# ampnshift.net
KiCad netlist of a schematic drawn in Altium Designer
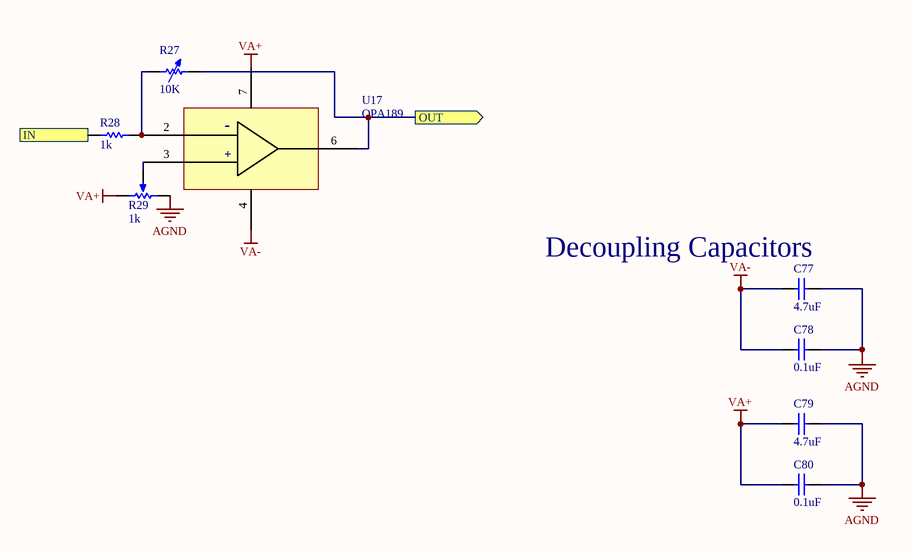
[diagram p0: ampnshift.SchDoc]

(export (version "E")
  (design (tool "Eeschema 10.0.6"))
  (components
    (comp (ref "C77")
      (value "4.7uF")
      (footprint "STD_0805_C")
      (description "Capacitor, 4.7uF, 0805")
      (libsource (lib "Arturo_Approved") (part "CL21A475KAQNNNE"))
    )
    (comp (ref "C78")
      (value "0.1uF")
      (footprint "STD_0805_C")
      (description "Capacitor, 0.1uF, 0805")
      (libsource (lib "Arturo_Approved") (part "CL21B104KACNNNC"))
    )
    (comp (ref "C79")
      (value "4.7uF")
      (footprint "STD_0805_C")
      (description "Capacitor, 4.7uF, 0805")
      (libsource (lib "Arturo_Approved") (part "CL21A475KAQNNNE"))
    )
    (comp (ref "C80")
      (value "0.1uF")
      (footprint "STD_0805_C")
      (description "Capacitor, 0.1uF, 0805")
      (libsource (lib "Arturo_Approved") (part "CL21B104KACNNNC"))
    )
    (comp (ref "R27")
      (value "10K")
      (footprint "TRIMRES")
      (description "Variable Resistor")
      (libsource (lib "Arturo_Approved") (part "3296W-1-103LF"))
    )
    (comp (ref "R28")
      (value "1k")
      (footprint "STD_0805_R")
      (description "1K 1% 1/4W")
      (libsource (lib "Arturo_Approved") (part "RNCP0805FTD1K00"))
    )
    (comp (ref "R29")
      (value "1k")
      (footprint "TRIMPOT")
      (description "Potentiometer, 1k")
      (libsource (lib "Arturo_Approved") (part "PV36W102C01B00"))
    )
    (comp (ref "U17")
      (value "OPA189")
      (footprint "SOIC_8")
      (description "Precision OpAmp, Generic")
      (libsource (lib "Arturo_Approved") (part "OPA189IDR"))
    )
  )
  (nets
    (net (code "1") (name "/IN") (class "Default")
      (node (ref "R28") (pin "1") (pinfunction "1_1") (pintype "passive"))
    )
    (net (code "2") (name "/OUT") (class "Default")
      (node (ref "R27") (pin "2") (pinfunction "2_2") (pintype "passive"))
      (node (ref "U17") (pin "6") (pintype "passive"))
    )
    (net (code "3") (name "AGND") (class "Default")
      (node (ref "C77") (pin "2") (pinfunction "2_2") (pintype "passive"))
      (node (ref "C78") (pin "2") (pinfunction "2_2") (pintype "passive"))
      (node (ref "C79") (pin "2") (pinfunction "2_2") (pintype "passive"))
      (node (ref "C80") (pin "2") (pinfunction "2_2") (pintype "passive"))
      (node (ref "R29") (pin "1") (pinfunction "TOP_1") (pintype "passive"))
    )
    (net (code "4") (name "Net-(R27-Pad1)") (class "Default")
      (node (ref "R27") (pin "1") (pinfunction "1_1") (pintype "passive"))
      (node (ref "R28") (pin "2") (pinfunction "2_2") (pintype "passive"))
      (node (ref "U17") (pin "2") (pintype "passive"))
    )
    (net (code "5") (name "Net-(R29-TAP)") (class "Default")
      (node (ref "R29") (pin "3") (pinfunction "TAP_3") (pintype "passive"))
      (node (ref "U17") (pin "3") (pintype "passive"))
    )
    (net (code "6") (name "VA+") (class "Default")
      (node (ref "C79") (pin "1") (pinfunction "1_1") (pintype "passive"))
      (node (ref "C80") (pin "1") (pinfunction "1_1") (pintype "passive"))
      (node (ref "R29") (pin "2") (pinfunction "BOT_2") (pintype "passive"))
      (node (ref "U17") (pin "7") (pintype "passive"))
    )
    (net (code "7") (name "VA-") (class "Default")
      (node (ref "C77") (pin "1") (pinfunction "1_1") (pintype "passive"))
      (node (ref "C78") (pin "1") (pinfunction "1_1") (pintype "passive"))
      (node (ref "U17") (pin "4") (pintype "passive"))
    )
  )
)
